# power2.net
KiCad netlist of a schematic drawn in Altium Designer
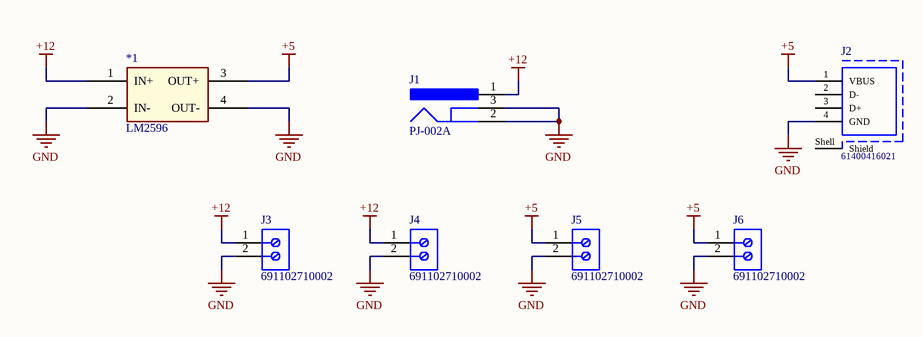
[diagram p0: power2.SchDoc]

(export (version "E")
  (design (tool "Eeschema 10.0.6"))
  (components
    (comp (ref "*1")
      (value "LM2596")
      (footprint "regulador")
      (description "LM2596 DC-DC")
      (libsource (lib "Componentes_PG") (part "regulador"))
    )
    (comp (ref "J1")
      (value "PJ-002A")
      (footprint "CUI-PJ-002A_V")
      (fields (field (name "MANUFACTURER") "CUIInc."))
      (libsource (lib "Altium Content Vault") (part "JACK-2CD3-RN_B"))
    )
    (comp (ref "J2")
      (value "61400416021")
      (footprint "61400416021")
      (description "USB 2.0 Type A Receptacle WR-COM, Horizontal, THT")
      (fields (field (name "MANUFACTURER") "Wurth Elektronik") (field (name "PUBLISHER") "WurthElektronik"))
      (libsource (lib "Altium Content Vault") (part "WE-USB-4-1SHLD"))
    )
    (comp (ref "J3")
      (value "691102710002")
      (footprint "691102710002")
      (description "Series 102 - 5.00 mm Horizontal Entry Modular with Pressure Clamp WR-TBL, 2 pin")
      (fields (field (name "MANUFACTURER") "Wurth Elektronik") (field (name "PUBLISHER") "WurthElektronik"))
      (libsource (lib "Altium Content Vault") (part "WE-CN-1P-F-TB2"))
    )
    (comp (ref "J4")
      (value "691102710002")
      (footprint "691102710002")
      (description "Series 102 - 5.00 mm Horizontal Entry Modular with Pressure Clamp WR-TBL, 2 pin")
      (fields (field (name "MANUFACTURER") "Wurth Elektronik") (field (name "PUBLISHER") "WurthElektronik"))
      (libsource (lib "Altium Content Vault") (part "WE-CN-1P-F-TB2"))
    )
    (comp (ref "J5")
      (value "691102710002")
      (footprint "691102710002")
      (description "Series 102 - 5.00 mm Horizontal Entry Modular with Pressure Clamp WR-TBL, 2 pin")
      (fields (field (name "MANUFACTURER") "Wurth Elektronik") (field (name "PUBLISHER") "WurthElektronik"))
      (libsource (lib "Altium Content Vault") (part "WE-CN-1P-F-TB2"))
    )
    (comp (ref "J6")
      (value "691102710002")
      (footprint "691102710002")
      (description "Series 102 - 5.00 mm Horizontal Entry Modular with Pressure Clamp WR-TBL, 2 pin")
      (fields (field (name "MANUFACTURER") "Wurth Elektronik") (field (name "PUBLISHER") "WurthElektronik"))
      (libsource (lib "Altium Content Vault") (part "WE-CN-1P-F-TB2"))
    )
  )
  (nets
    (net (code "1") (name "+5") (class "Default")
      (node (ref "*1") (pin "3") (pinfunction "OUT+_3") (pintype "passive"))
      (node (ref "J2") (pin "1") (pinfunction "VBUS_1") (pintype "passive"))
      (node (ref "J5") (pin "1") (pinfunction "1_1") (pintype "passive"))
      (node (ref "J6") (pin "1") (pinfunction "1_1") (pintype "passive"))
    )
    (net (code "2") (name "+12") (class "Default")
      (node (ref "*1") (pin "1") (pinfunction "IN+_1") (pintype "passive"))
      (node (ref "J1") (pin "1") (pinfunction "1_1") (pintype "passive"))
      (node (ref "J3") (pin "1") (pinfunction "1_1") (pintype "passive"))
      (node (ref "J4") (pin "1") (pinfunction "1_1") (pintype "passive"))
    )
    (net (code "3") (name "GND") (class "Default")
      (node (ref "*1") (pin "2") (pinfunction "IN-_2") (pintype "passive"))
      (node (ref "*1") (pin "4") (pinfunction "OUT-_4") (pintype "passive"))
      (node (ref "J1") (pin "2") (pinfunction "2_2") (pintype "passive"))
      (node (ref "J1") (pin "3") (pinfunction "3_3") (pintype "passive"))
      (node (ref "J2") (pin "4") (pinfunction "GND_4") (pintype "passive"))
      (node (ref "J3") (pin "2") (pinfunction "2_2") (pintype "passive"))
      (node (ref "J4") (pin "2") (pinfunction "2_2") (pintype "passive"))
      (node (ref "J5") (pin "2") (pinfunction "2_2") (pintype "passive"))
      (node (ref "J6") (pin "2") (pinfunction "2_2") (pintype "passive"))
    )
    (net (code "4") (name "unconnected-(J2-D+-Pad3)") (class "Default")
      (node (ref "J2") (pin "3") (pinfunction "D+_3") (pintype "passive"))
    )
    (net (code "5") (name "unconnected-(J2-D--Pad2)") (class "Default")
      (node (ref "J2") (pin "2") (pinfunction "D-_2") (pintype "passive"))
    )
    (net (code "6") (name "unconnected-(J2-Shield-PadShell)") (class "Default")
      (node (ref "J2") (pin "Shell") (pinfunction "Shield_Shell") (pintype "passive"))
    )
  )
)
